# simple_clock.net
KiCad netlist of a schematic drawn in EAGLE
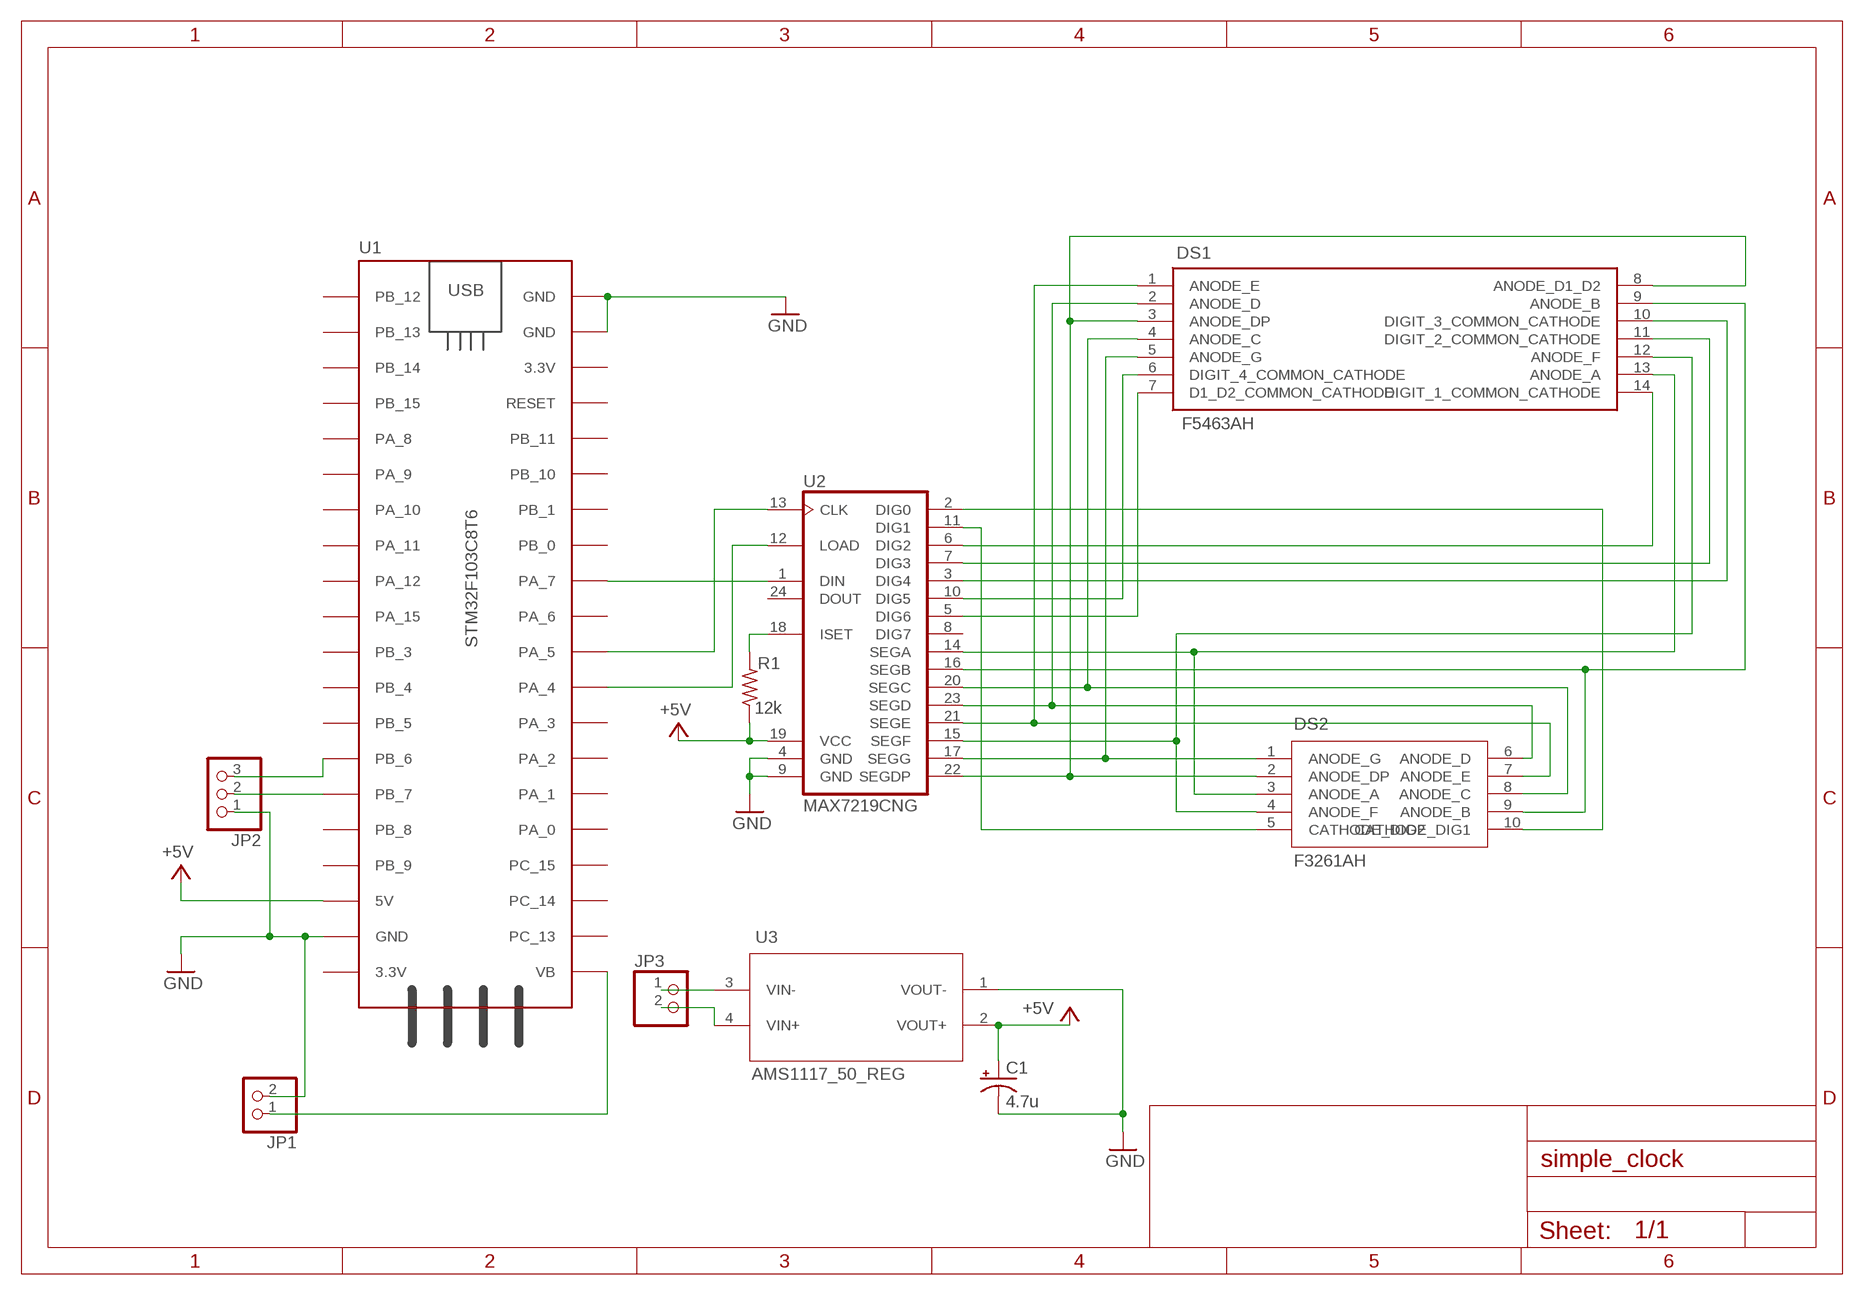
[diagram p0: schematic, sheet 1]

(export (version "E")
  (design (tool "Eeschema 10.0.6"))
  (components
    (comp (ref "C1")
      (value "4.7u")
      (footprint "eagle-import:E1,8-4")
      (libsource (lib "eagle-import") (part "CPOL-USE1.8-4"))
    )
    (comp (ref "DS1")
      (value "F5463AH")
      (footprint "eagle-import:F5463AH")
      (libsource (lib "eagle-import") (part "F5463AH"))
    )
    (comp (ref "DS2")
      (value "F3261AH")
      (footprint "eagle-import:F3261AH")
      (libsource (lib "eagle-import") (part "F3261AH"))
    )
    (comp (ref "JP1")
      (value "PINHD-1X2")
      (footprint "eagle-import:1X02")
      (libsource (lib "eagle-import") (part "PINHD-1X2"))
    )
    (comp (ref "JP2")
      (value "PINHD-1X3")
      (footprint "eagle-import:1X03")
      (libsource (lib "eagle-import") (part "PINHD-1X3"))
    )
    (comp (ref "JP3")
      (value "PINHD-1X2")
      (footprint "eagle-import:1X02")
      (libsource (lib "eagle-import") (part "PINHD-1X2"))
    )
    (comp (ref "R1")
      (value "12k")
      (footprint "eagle-import:0207_12")
      (libsource (lib "eagle-import") (part "R-US_0207/12"))
    )
    (comp (ref "U1")
      (value "STM32F103C8T6")
      (footprint "eagle-import:STM32F103C8T6")
      (libsource (lib "eagle-import") (part "STM32F103C8T6"))
    )
    (comp (ref "U2")
      (value "MAX7219CNG")
      (footprint "eagle-import:DIL24-3")
      (fields (field (name "MF") "MAXIM"))
      (libsource (lib "eagle-import") (part "MAX7219CNG"))
    )
    (comp (ref "U3")
      (value "AMS1117_50_REG")
      (footprint "eagle-import:AMS1117_50_REG")
      (libsource (lib "eagle-import") (part "AMS1117_50_REG"))
    )
  )
  (nets
    (net (code "1") (name "+5V") (class "Default")
      (node (ref "C1") (pin "+") (pinfunction "+_+") (pintype "passive"))
      (node (ref "R1") (pin "1") (pinfunction "1_1") (pintype "passive"))
      (node (ref "U1") (pin "5V") (pinfunction "5V_5V") (pintype "bidirectional"))
      (node (ref "U2") (pin "19") (pinfunction "VCC_19") (pintype "power_in"))
      (node (ref "U3") (pin "2") (pinfunction "VOUT+_2") (pintype "bidirectional"))
    )
    (net (code "2") (name "GND") (class "Default")
      (node (ref "C1") (pin "-") (pinfunction "-_-") (pintype "passive"))
      (node (ref "JP1") (pin "2") (pinfunction "2_2") (pintype "passive"))
      (node (ref "JP2") (pin "1") (pinfunction "1_1") (pintype "passive"))
      (node (ref "U1") (pin "GND_1") (pinfunction "GND_GND_1") (pintype "bidirectional"))
      (node (ref "U1") (pin "GND_2") (pinfunction "GND_GND_2") (pintype "bidirectional"))
      (node (ref "U1") (pin "GND_3") (pinfunction "GND_GND_3") (pintype "power_in"))
      (node (ref "U2") (pin "4") (pinfunction "GND_4") (pintype "power_in"))
      (node (ref "U2") (pin "9") (pinfunction "GND_9") (pintype "power_in"))
      (node (ref "U3") (pin "1") (pinfunction "VOUT-_1") (pintype "bidirectional"))
    )
    (net (code "3") (name "Net-(DS1-ANODE_A)") (class "Default")
      (node (ref "DS1") (pin "13") (pinfunction "ANODE_A_13") (pintype "bidirectional"))
      (node (ref "DS2") (pin "3") (pinfunction "ANODE_A_3") (pintype "bidirectional"))
      (node (ref "U2") (pin "14") (pinfunction "SEGA_14") (pintype "output"))
    )
    (net (code "4") (name "Net-(DS1-ANODE_B)") (class "Default")
      (node (ref "DS1") (pin "9") (pinfunction "ANODE_B_9") (pintype "bidirectional"))
      (node (ref "DS2") (pin "9") (pinfunction "ANODE_B_9") (pintype "bidirectional"))
      (node (ref "U2") (pin "16") (pinfunction "SEGB_16") (pintype "output"))
    )
    (net (code "5") (name "Net-(DS1-ANODE_C)") (class "Default")
      (node (ref "DS1") (pin "4") (pinfunction "ANODE_C_4") (pintype "bidirectional"))
      (node (ref "DS2") (pin "8") (pinfunction "ANODE_C_8") (pintype "bidirectional"))
      (node (ref "U2") (pin "20") (pinfunction "SEGC_20") (pintype "output"))
    )
    (net (code "6") (name "Net-(DS1-ANODE_D)") (class "Default")
      (node (ref "DS1") (pin "2") (pinfunction "ANODE_D_2") (pintype "bidirectional"))
      (node (ref "DS2") (pin "6") (pinfunction "ANODE_D_6") (pintype "bidirectional"))
      (node (ref "U2") (pin "23") (pinfunction "SEGD_23") (pintype "output"))
    )
    (net (code "7") (name "Net-(DS1-ANODE_D1_D2)") (class "Default")
      (node (ref "DS1") (pin "3") (pinfunction "ANODE_DP_3") (pintype "bidirectional"))
      (node (ref "DS1") (pin "8") (pinfunction "ANODE_D1_D2_8") (pintype "bidirectional"))
      (node (ref "DS2") (pin "2") (pinfunction "ANODE_DP_2") (pintype "bidirectional"))
      (node (ref "U2") (pin "22") (pinfunction "SEGDP_22") (pintype "output"))
    )
    (net (code "8") (name "Net-(DS1-ANODE_E)") (class "Default")
      (node (ref "DS1") (pin "1") (pinfunction "ANODE_E_1") (pintype "bidirectional"))
      (node (ref "DS2") (pin "7") (pinfunction "ANODE_E_7") (pintype "bidirectional"))
      (node (ref "U2") (pin "21") (pinfunction "SEGE_21") (pintype "output"))
    )
    (net (code "9") (name "Net-(DS1-ANODE_F)") (class "Default")
      (node (ref "DS1") (pin "12") (pinfunction "ANODE_F_12") (pintype "bidirectional"))
      (node (ref "DS2") (pin "4") (pinfunction "ANODE_F_4") (pintype "bidirectional"))
      (node (ref "U2") (pin "15") (pinfunction "SEGF_15") (pintype "output"))
    )
    (net (code "10") (name "Net-(DS1-ANODE_G)") (class "Default")
      (node (ref "DS1") (pin "5") (pinfunction "ANODE_G_5") (pintype "bidirectional"))
      (node (ref "DS2") (pin "1") (pinfunction "ANODE_G_1") (pintype "bidirectional"))
      (node (ref "U2") (pin "17") (pinfunction "SEGG_17") (pintype "output"))
    )
    (net (code "11") (name "Net-(DS1-D1_D2_COMMON_CATHODE)") (class "Default")
      (node (ref "DS1") (pin "7") (pinfunction "D1_D2_COMMON_CATHODE_7") (pintype "bidirectional"))
      (node (ref "U2") (pin "5") (pinfunction "DIG6_5") (pintype "output"))
    )
    (net (code "12") (name "Net-(DS1-DIGIT_1_COMMON_CATHODE)") (class "Default")
      (node (ref "DS1") (pin "14") (pinfunction "DIGIT_1_COMMON_CATHODE_14") (pintype "bidirectional"))
      (node (ref "U2") (pin "6") (pinfunction "DIG2_6") (pintype "output"))
    )
    (net (code "13") (name "Net-(DS1-DIGIT_2_COMMON_CATHODE)") (class "Default")
      (node (ref "DS1") (pin "11") (pinfunction "DIGIT_2_COMMON_CATHODE_11") (pintype "bidirectional"))
      (node (ref "U2") (pin "7") (pinfunction "DIG3_7") (pintype "output"))
    )
    (net (code "14") (name "Net-(DS1-DIGIT_3_COMMON_CATHODE)") (class "Default")
      (node (ref "DS1") (pin "10") (pinfunction "DIGIT_3_COMMON_CATHODE_10") (pintype "bidirectional"))
      (node (ref "U2") (pin "3") (pinfunction "DIG4_3") (pintype "output"))
    )
    (net (code "15") (name "Net-(DS1-DIGIT_4_COMMON_CATHODE)") (class "Default")
      (node (ref "DS1") (pin "6") (pinfunction "DIGIT_4_COMMON_CATHODE_6") (pintype "bidirectional"))
      (node (ref "U2") (pin "10") (pinfunction "DIG5_10") (pintype "output"))
    )
    (net (code "16") (name "Net-(DS2-CATHODE_DIG1)") (class "Default")
      (node (ref "DS2") (pin "10") (pinfunction "CATHODE_DIG1_10") (pintype "bidirectional"))
      (node (ref "U2") (pin "2") (pinfunction "DIG0_2") (pintype "output"))
    )
    (net (code "17") (name "Net-(DS2-CATHODE_DIG2)") (class "Default")
      (node (ref "DS2") (pin "5") (pinfunction "CATHODE_DIG2_5") (pintype "bidirectional"))
      (node (ref "U2") (pin "11") (pinfunction "DIG1_11") (pintype "output"))
    )
    (net (code "18") (name "Net-(JP1-Pad1)") (class "Default")
      (node (ref "JP1") (pin "1") (pinfunction "1_1") (pintype "passive"))
      (node (ref "U1") (pin "VB") (pinfunction "VB_VB") (pintype "bidirectional"))
    )
    (net (code "19") (name "Net-(JP2-Pad2)") (class "Default")
      (node (ref "JP2") (pin "2") (pinfunction "2_2") (pintype "passive"))
      (node (ref "U1") (pin "PB_7") (pinfunction "PB_7_PB_7") (pintype "bidirectional"))
    )
    (net (code "20") (name "Net-(JP2-Pad3)") (class "Default")
      (node (ref "JP2") (pin "3") (pinfunction "3_3") (pintype "passive"))
      (node (ref "U1") (pin "PB_6") (pinfunction "PB_6_PB_6") (pintype "bidirectional"))
    )
    (net (code "21") (name "Net-(U2-CLK)") (class "Default")
      (node (ref "U1") (pin "PA_5") (pinfunction "PA_5_PA_5") (pintype "bidirectional"))
      (node (ref "U2") (pin "13") (pinfunction "CLK_13") (pintype "input"))
    )
    (net (code "22") (name "Net-(U2-DIN)") (class "Default")
      (node (ref "U1") (pin "PA_7") (pinfunction "PA_7_PA_7") (pintype "bidirectional"))
      (node (ref "U2") (pin "1") (pinfunction "DIN_1") (pintype "input"))
    )
    (net (code "23") (name "Net-(U2-ISET)") (class "Default")
      (node (ref "R1") (pin "2") (pinfunction "2_2") (pintype "passive"))
      (node (ref "U2") (pin "18") (pinfunction "ISET_18") (pintype "input"))
    )
    (net (code "24") (name "Net-(U2-LOAD)") (class "Default")
      (node (ref "U1") (pin "PA_4") (pinfunction "PA_4_PA_4") (pintype "bidirectional"))
      (node (ref "U2") (pin "12") (pinfunction "LOAD_12") (pintype "input"))
    )
    (net (code "25") (name "Net-(U3-VIN+)") (class "Default")
      (node (ref "JP3") (pin "2") (pinfunction "2_2") (pintype "passive"))
      (node (ref "U3") (pin "4") (pinfunction "VIN+_4") (pintype "bidirectional"))
    )
    (net (code "26") (name "Net-(U3-VIN-)") (class "Default")
      (node (ref "JP3") (pin "1") (pinfunction "1_1") (pintype "passive"))
      (node (ref "U3") (pin "3") (pinfunction "VIN-_3") (pintype "bidirectional"))
    )
    (net (code "27") (name "unconnected-(U1-3.3V-Pad3.3V_1)") (class "Default")
      (node (ref "U1") (pin "3.3V_1") (pinfunction "3.3V_3.3V_1") (pintype "bidirectional"))
    )
    (net (code "28") (name "unconnected-(U1-3.3V-Pad3.3V_2)") (class "Default")
      (node (ref "U1") (pin "3.3V_2") (pinfunction "3.3V_3.3V_2") (pintype "bidirectional"))
    )
    (net (code "29") (name "unconnected-(U1-PadPA_0)") (class "Default")
      (node (ref "U1") (pin "PA_0") (pinfunction "PA_0_PA_0") (pintype "bidirectional"))
    )
    (net (code "30") (name "unconnected-(U1-PadPA_1)") (class "Default")
      (node (ref "U1") (pin "PA_1") (pinfunction "PA_1_PA_1") (pintype "bidirectional"))
    )
    (net (code "31") (name "unconnected-(U1-PadPA_2)") (class "Default")
      (node (ref "U1") (pin "PA_2") (pinfunction "PA_2_PA_2") (pintype "bidirectional"))
    )
    (net (code "32") (name "unconnected-(U1-PadPA_3)") (class "Default")
      (node (ref "U1") (pin "PA_3") (pinfunction "PA_3_PA_3") (pintype "bidirectional"))
    )
    (net (code "33") (name "unconnected-(U1-PadPA_6)") (class "Default")
      (node (ref "U1") (pin "PA_6") (pinfunction "PA_6_PA_6") (pintype "bidirectional"))
    )
    (net (code "34") (name "unconnected-(U1-PadPA_8)") (class "Default")
      (node (ref "U1") (pin "PA_8") (pinfunction "PA_8_PA_8") (pintype "bidirectional"))
    )
    (net (code "35") (name "unconnected-(U1-PadPA_9)") (class "Default")
      (node (ref "U1") (pin "PA_9") (pinfunction "PA_9_PA_9") (pintype "bidirectional"))
    )
    (net (code "36") (name "unconnected-(U1-PadPA_10)") (class "Default")
      (node (ref "U1") (pin "PA_10") (pinfunction "PA_10_PA_10") (pintype "bidirectional"))
    )
    (net (code "37") (name "unconnected-(U1-PadPA_11)") (class "Default")
      (node (ref "U1") (pin "PA_11") (pinfunction "PA_11_PA_11") (pintype "bidirectional"))
    )
    (net (code "38") (name "unconnected-(U1-PadPA_12)") (class "Default")
      (node (ref "U1") (pin "PA_12") (pinfunction "PA_12_PA_12") (pintype "bidirectional"))
    )
    (net (code "39") (name "unconnected-(U1-PadPA_15)") (class "Default")
      (node (ref "U1") (pin "PA_15") (pinfunction "PA_15_PA_15") (pintype "bidirectional"))
    )
    (net (code "40") (name "unconnected-(U1-PadPB_0)") (class "Default")
      (node (ref "U1") (pin "PB_0") (pinfunction "PB_0_PB_0") (pintype "bidirectional"))
    )
    (net (code "41") (name "unconnected-(U1-PadPB_1)") (class "Default")
      (node (ref "U1") (pin "PB_1") (pinfunction "PB_1_PB_1") (pintype "bidirectional"))
    )
    (net (code "42") (name "unconnected-(U1-PadPB_3)") (class "Default")
      (node (ref "U1") (pin "PB_3") (pinfunction "PB_3_PB_3") (pintype "bidirectional"))
    )
    (net (code "43") (name "unconnected-(U1-PadPB_4)") (class "Default")
      (node (ref "U1") (pin "PB_4") (pinfunction "PB_4_PB_4") (pintype "bidirectional"))
    )
    (net (code "44") (name "unconnected-(U1-PadPB_5)") (class "Default")
      (node (ref "U1") (pin "PB_5") (pinfunction "PB_5_PB_5") (pintype "bidirectional"))
    )
    (net (code "45") (name "unconnected-(U1-PadPB_8)") (class "Default")
      (node (ref "U1") (pin "PB_8") (pinfunction "PB_8_PB_8") (pintype "bidirectional"))
    )
    (net (code "46") (name "unconnected-(U1-PadPB_9)") (class "Default")
      (node (ref "U1") (pin "PB_9") (pinfunction "PB_9_PB_9") (pintype "bidirectional"))
    )
    (net (code "47") (name "unconnected-(U1-PadPB_10)") (class "Default")
      (node (ref "U1") (pin "PB_10") (pinfunction "PB_10_PB_10") (pintype "bidirectional"))
    )
    (net (code "48") (name "unconnected-(U1-PadPB_11)") (class "Default")
      (node (ref "U1") (pin "PB_11") (pinfunction "PB_11_PB_11") (pintype "bidirectional"))
    )
    (net (code "49") (name "unconnected-(U1-PadPB_12)") (class "Default")
      (node (ref "U1") (pin "PB_12") (pinfunction "PB_12_PB_12") (pintype "bidirectional"))
    )
    (net (code "50") (name "unconnected-(U1-PadPB_13)") (class "Default")
      (node (ref "U1") (pin "PB_13") (pinfunction "PB_13_PB_13") (pintype "bidirectional"))
    )
    (net (code "51") (name "unconnected-(U1-PadPB_14)") (class "Default")
      (node (ref "U1") (pin "PB_14") (pinfunction "PB_14_PB_14") (pintype "bidirectional"))
    )
    (net (code "52") (name "unconnected-(U1-PadPB_15)") (class "Default")
      (node (ref "U1") (pin "PB_15") (pinfunction "PB_15_PB_15") (pintype "bidirectional"))
    )
    (net (code "53") (name "unconnected-(U1-PadPC_13)") (class "Default")
      (node (ref "U1") (pin "PC_13") (pinfunction "PC_13_PC_13") (pintype "bidirectional"))
    )
    (net (code "54") (name "unconnected-(U1-PadPC_14)") (class "Default")
      (node (ref "U1") (pin "PC_14") (pinfunction "PC_14_PC_14") (pintype "bidirectional"))
    )
    (net (code "55") (name "unconnected-(U1-PadPC_15)") (class "Default")
      (node (ref "U1") (pin "PC_15") (pinfunction "PC_15_PC_15") (pintype "bidirectional"))
    )
    (net (code "56") (name "unconnected-(U1-PadRESET)") (class "Default")
      (node (ref "U1") (pin "RESET") (pinfunction "RESET_RESET") (pintype "bidirectional"))
    )
    (net (code "57") (name "unconnected-(U2-DIG7-Pad8)") (class "Default")
      (node (ref "U2") (pin "8") (pinfunction "DIG7_8") (pintype "output"))
    )
    (net (code "58") (name "unconnected-(U2-DOUT-Pad24)") (class "Default")
      (node (ref "U2") (pin "24") (pinfunction "DOUT_24") (pintype "output"))
    )
  )
)
